# LiPo_Charger.net
KiCad netlist of a schematic drawn in Altium Designer
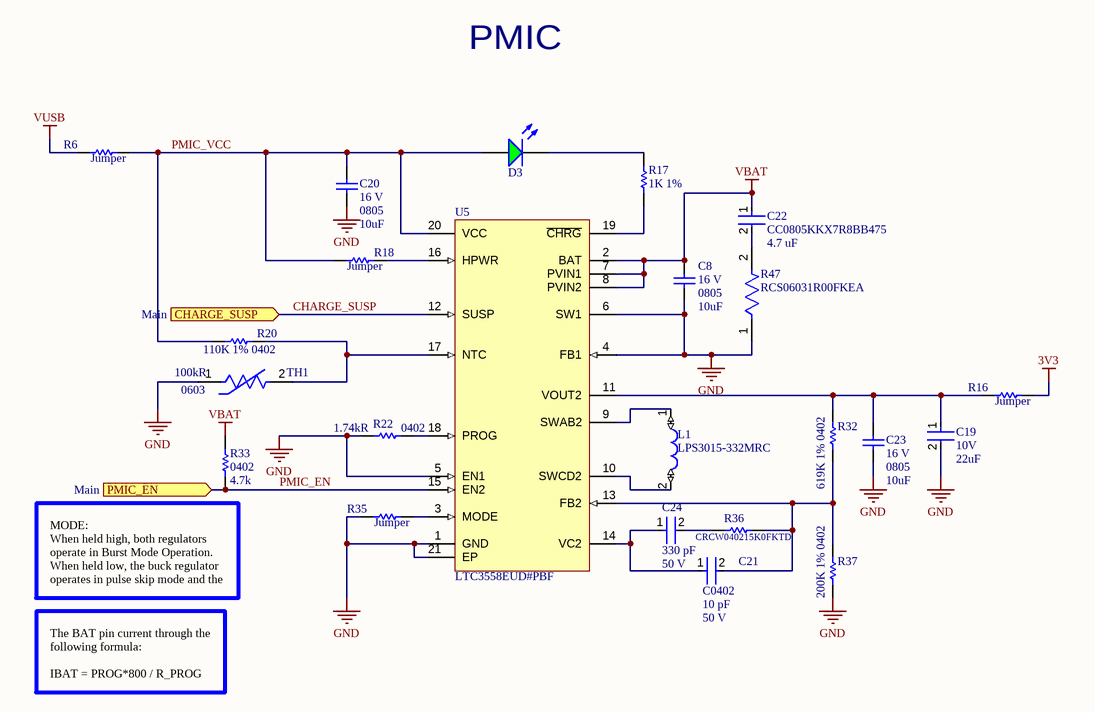
[diagram p0: LiPo_Charger.SchDoc]

(export (version "E")
  (design (tool "Eeschema 10.0.6"))
  (components
    (comp (ref "C8")
      (value "10uF")
      (footprint "CAPC0805(2012)145_N")
      (description "CAP 10uF 16V ±10% 0805 (2012 Metric) Thickness 1.45mm SMD")
      (fields
        (field (name "RATED VOLTAGE") "16 V")
        (field (name "CASE-EIA") "0805")
        (field (name "TOLERANCE") "Â±10%")
        (field (name "MANUFACTURER PART NUMBER") "CC0805KKX7R7BB106")
      )
      (libsource (lib "ProtoWatch_Compiled") (part "CMP-1036-04927-1"))
    )
    (comp (ref "C19")
      (value "LMK107BBJ226MA-T")
      (footprint "FP-LMK107B-A-MFG")
      (description "CAP CER 22UF 10V X5R 0603")
      (fields
        (field (name "TOLERANCE") "20%")
        (field (name "MANUFACTURER") "Taiyo Yuden")
        (field (name "VOLTAGE RATING") "10V")
        (field (name "CAPACITANCE") "22uF")
      )
      (libsource (lib "Altium Content Vault") (part "11868f565c42a9108669ba33697ecf6"))
    )
    (comp (ref "C20")
      (value "10uF")
      (footprint "CAPC0805(2012)145_N")
      (description "CAP 10uF 16V ±10% 0805 (2012 Metric) Thickness 1.45mm SMD")
      (fields
        (field (name "RATED VOLTAGE") "16 V")
        (field (name "CASE-EIA") "0805")
        (field (name "TOLERANCE") "Â±10%")
        (field (name "MANUFACTURER PART NUMBER") "CC0805KKX7R7BB106")
      )
      (libsource (lib "ProtoWatch_Compiled") (part "CMP-1036-04927-1"))
    )
    (comp (ref "C21")
      (value "10 pF")
      (footprint "FP-C0402-BB-MFG")
      (description "C0402 10 pF C0G 0.5 pF 50 V")
      (fields
        (field (name "MANUFACTURER") "Kemet")
        (field (name "PACKAGE") "C0402")
        (field (name "OCTOPART") "https://octopart.com/c0402c100d5gac-kemet-2680337")
        (field (name "VOLTAGE RATING") "50 V")
      )
      (libsource (lib "Altium Content Vault") (part "b4654b650e69147ec39a6b967a45e02"))
    )
    (comp (ref "C22")
      (value "CC0805KKX7R8BB475")
      (footprint "FP-CC0805-0_85-MFG")
      (description "CAP CER 4.7UF 25V X7R 0805")
      (fields
        (field (name "OCTOPART") "https://octopart.com/cc0805kkx7r8bb475-yageo-51849247")
        (field (name "CAPACITANCE") "4.7 uF")
        (field (name "MANUFACTURER") "Yageo")
      )
      (libsource (lib "Altium Content Vault") (part "11868f565c42a9108669ba33697ecf6"))
    )
    (comp (ref "C23")
      (value "10uF")
      (footprint "CAPC0805(2012)145_N")
      (description "CAP 10uF 16V ±10% 0805 (2012 Metric) Thickness 1.45mm SMD")
      (fields
        (field (name "RATED VOLTAGE") "16 V")
        (field (name "CASE-EIA") "0805")
        (field (name "TOLERANCE") "Â±10%")
        (field (name "MANUFACTURER PART NUMBER") "CC0805KKX7R7BB106")
      )
      (libsource (lib "ProtoWatch_Compiled") (part "CMP-1036-04927-1"))
    )
    (comp (ref "C24")
      (value "330 pF")
      (footprint "FP-CC0402-MFG")
      (description "CAP CER 330PF 50V X7R 0402")
      (fields
        (field (name "MANUFACTURER") "YAGEO")
        (field (name "MANUFACTURER PART NUMBER") "CC0402KRX7R9BB331")
        (field (name "VOLTAGE RATING") "50 V")
      )
      (libsource (lib "Altium Content Vault") (part "11868f565c42a9108669ba33697ecf6"))
    )
    (comp (ref "D3")
      (value "LTST-C170GKT")
      (footprint "LTST-C170GKT_V")
      (description "LED Uni-Color Green, 100 mW, 120 mA, -55 to 85 degC, 2-Pin SMD, RoHS, Tape and Reel")
      (fields (field (name "MANUFACTURER") "Lite-On"))
      (libsource (lib "Altium Content Vault") (part "LED-GREEN-AK-2"))
    )
    (comp (ref "L1")
      (value "LPS3015-332MRC")
      (footprint "ProtoWatch_PcbLib:LPS3015")
      (description "Power inductor, shielded, 20% tol, SMT, RoHS, lead-free, halogen-free")
      (fields (field (name "MF") "Coilcraft"))
      (libsource (lib "ProtoWatch_SchLib") (part "LPS3015-332MRC"))
    )
    (comp (ref "R6")
      (value "Jumper")
      (footprint "RESC0603(1608)_N")
      (description "Jumper 0603 (1608 Metric)")
      (fields (field (name "POWER") "None"))
      (libsource (lib "Altium Content Vault") (part "RES"))
    )
    (comp (ref "R16")
      (value "Jumper")
      (footprint "RESC0603(1608)_N")
      (description "Jumper 0603 (1608 Metric)")
      (fields (field (name "POWER") "None"))
      (libsource (lib "Altium Content Vault") (part "RES"))
    )
    (comp (ref "R17")
      (value "1K 1%")
      (footprint "RESC0603(1608)_N")
      (description "1K 0.1W 1% 0603 (1608 Metric)  SMD")
      (fields (field (name "TOLERANCE") "1 %") (field (name "POWER") "0.1 W"))
      (libsource (lib "Altium Content Vault") (part "RES"))
    )
    (comp (ref "R18")
      (value "Jumper")
      (footprint "RESC0603(1608)_N")
      (description "Jumper 0603 (1608 Metric)")
      (fields (field (name "POWER") "None"))
      (libsource (lib "Altium Content Vault") (part "RES"))
    )
    (comp (ref "R20")
      (value "110K 1% 0402")
      (footprint "RESC0402(1005)_M")
      (description "110K 0.063W 1% 0402 (1005 Metric)  SMD")
      (fields (field (name "TOLERANCE") "1 %") (field (name "POWER") "0.063 W"))
      (libsource (lib "Altium Content Vault") (part "RES"))
    )
    (comp (ref "R22")
      (value "CRCW04021K74FKED")
      (footprint "RESC1005X40X25LL05T05")
      (fields
        (field (name "MANUFACTURER") "Vishay Dale")
        (field (name "CASE/PACKAGE") "0402")
        (field (name "TOLERANCE") "1%")
        (field (name "RESISTANCE") "1.74kR")
      )
      (libsource (lib "Altium Content Vault") (part "RES"))
    )
    (comp (ref "R32")
      (value "619K 1% 0402")
      (footprint "RESC0402(1005)_L")
      (description "619K 0.063W 1% 0402 (1005 Metric)  SMD")
      (fields (field (name "POWER") "0.063 W") (field (name "TOLERANCE") "1 %"))
      (libsource (lib "Altium Content Vault") (part "RES"))
    )
    (comp (ref "R33")
      (value "RMCF0402JT4K70")
      (footprint "RESC1005X40X25LL10T15")
      (description "Chip Resistor, 4.7 KOhm, +/- 5%, 0.063 W, -55 to 155 degC, 0402 (1005 Metric), RoHS, Tape and Reel")
      (fields
        (field (name "MANUFACTURER") "Stackpole-Electronics-Inc.")
        (field (name "TOLERANCE") "±5%")
        (field (name "PACKAGE REFERENCE") "0402")
        (field (name "RESISTANCE (OHMS)") "4.7k")
      )
      (libsource (lib "Altium Content Vault") (part "RES-2"))
    )
    (comp (ref "R35")
      (value "Jumper")
      (footprint "RESC0603(1608)_N")
      (description "Jumper 0603 (1608 Metric)")
      (fields (field (name "POWER") "None"))
      (libsource (lib "Altium Content Vault") (part "RES"))
    )
    (comp (ref "R36")
      (value "CRCW040215K0FKTD")
      (footprint "RESC1005X40X25NL05T05")
      (fields (field (name "MANUFACTURER") "Vishay Dale"))
      (libsource (lib "Altium Content Vault") (part "RES"))
    )
    (comp (ref "R37")
      (value "200K 1% 0402")
      (footprint "RESC0402(1005)_L")
      (description "200K 0.063W 1% 0402 (1005 Metric)  SMD")
      (fields (field (name "TOLERANCE") "1 %") (field (name "POWER") "0.063 W"))
      (libsource (lib "Altium Content Vault") (part "RES"))
    )
    (comp (ref "R47")
      (value "RCS06031R00FKEA")
      (footprint "FP-RCS0603-e3-MFG")
      (description "RES SMD 1 OHM 1% 1/4W 0603")
      (fields (field (name "TOLERANCE") "1%"))
      (libsource (lib "Altium Content Vault") (part "1029c3af85768c4190bb7ad29bc67b5"))
    )
    (comp (ref "TH1")
      (value "NCP18WF104D03RB")
      (footprint "FP-NCP18-0_15-MFG")
      (description "NTC Thermistor for Temperature Sensor, 0603, 100kΩ, 0.5%, 0.032mA, 5V")
      (fields
        (field (name "TOLERANCE") "0.5%")
        (field (name "CASE CODE (IMPERIAL)") "0603")
        (field (name "RESISTANCE") "100kR")
      )
      (libsource (lib "Altium Content Vault") (part "3b148a6ebabc5fb4d708a66c052d352"))
    )
    (comp (ref "U5")
      (value "LTC3558EUD#PBF")
      (footprint "LT-UD-20_N")
      (fields (field (name "MANUFACTURER") "Linear Technology"))
      (libsource (lib "ProtoWatch_SchLib") (part "LTC3558EUD#PBF"))
    )
  )
  (nets
    (net (code "1") (name "/CHARGE_SUSP") (class "Default")
      (node (ref "U5") (pin "12") (pinfunction "SUSP_12") (pintype "input"))
    )
    (net (code "2") (name "/PMIC_EN") (class "Default")
      (node (ref "R33") (pin "1") (pinfunction "1_1") (pintype "passive"))
      (node (ref "U5") (pin "15") (pinfunction "EN2_15") (pintype "input"))
    )
    (net (code "3") (name "/PMIC_VCC") (class "Default")
      (node (ref "C20") (pin "2") (pinfunction "2_2") (pintype "passive"))
      (node (ref "D3") (pin "1") (pinfunction "A_1") (pintype "passive"))
      (node (ref "R18") (pin "1") (pinfunction "1_1") (pintype "passive"))
      (node (ref "R20") (pin "1") (pinfunction "1_1") (pintype "passive"))
      (node (ref "R6") (pin "2") (pinfunction "2_2") (pintype "passive"))
      (node (ref "U5") (pin "20") (pinfunction "VCC_20") (pintype "passive"))
    )
    (net (code "4") (name "3V3") (class "Default")
      (node (ref "R16") (pin "2") (pinfunction "2_2") (pintype "passive"))
    )
    (net (code "5") (name "GND") (class "Default")
      (node (ref "C19") (pin "2") (pinfunction "2_2") (pintype "passive"))
      (node (ref "C20") (pin "1") (pinfunction "1_1") (pintype "passive"))
      (node (ref "C23") (pin "1") (pinfunction "1_1") (pintype "passive"))
      (node (ref "C8") (pin "1") (pinfunction "1_1") (pintype "passive"))
      (node (ref "R22") (pin "1") (pinfunction "1_1") (pintype "passive"))
      (node (ref "R35") (pin "1") (pinfunction "1_1") (pintype "passive"))
      (node (ref "R37") (pin "2") (pinfunction "2_2") (pintype "passive"))
      (node (ref "R47") (pin "1") (pinfunction "1_1") (pintype "passive"))
      (node (ref "TH1") (pin "1") (pinfunction "1_1") (pintype "passive"))
      (node (ref "U5") (pin "1") (pinfunction "GND_1") (pintype "power_in"))
      (node (ref "U5") (pin "21") (pinfunction "EP_21") (pintype "power_in"))
      (node (ref "U5") (pin "4") (pinfunction "FB1_4") (pintype "input"))
      (node (ref "U5") (pin "5") (pinfunction "EN1_5") (pintype "input"))
      (node (ref "U5") (pin "6") (pinfunction "SW1_6") (pintype "power_in"))
    )
    (net (code "6") (name "Net-(C22-Pad2)") (class "Default")
      (node (ref "C22") (pin "2") (pinfunction "2_2") (pintype "passive"))
      (node (ref "R47") (pin "2") (pinfunction "2_2") (pintype "passive"))
    )
    (net (code "7") (name "Net-(C24-Pad2)") (class "Default")
      (node (ref "C24") (pin "2") (pinfunction "2_2") (pintype "passive"))
      (node (ref "R36") (pin "1") (pinfunction "1_1") (pintype "passive"))
    )
    (net (code "8") (name "Net-(D3-K)") (class "Default")
      (node (ref "D3") (pin "2") (pinfunction "K_2") (pintype "passive"))
      (node (ref "R17") (pin "1") (pinfunction "1_1") (pintype "passive"))
    )
    (net (code "9") (name "Net-(U5-FB2)") (class "Default")
      (node (ref "C21") (pin "2") (pinfunction "2_2") (pintype "passive"))
      (node (ref "R32") (pin "1") (pinfunction "1_1") (pintype "passive"))
      (node (ref "R36") (pin "2") (pinfunction "2_2") (pintype "passive"))
      (node (ref "R37") (pin "1") (pinfunction "1_1") (pintype "passive"))
      (node (ref "U5") (pin "13") (pinfunction "FB2_13") (pintype "input"))
    )
    (net (code "10") (name "Net-(U5-HPWR)") (class "Default")
      (node (ref "R18") (pin "2") (pinfunction "2_2") (pintype "passive"))
      (node (ref "U5") (pin "16") (pinfunction "HPWR_16") (pintype "input"))
    )
    (net (code "11") (name "Net-(U5-MODE)") (class "Default")
      (node (ref "R35") (pin "2") (pinfunction "2_2") (pintype "passive"))
      (node (ref "U5") (pin "3") (pinfunction "MODE_3") (pintype "input"))
    )
    (net (code "12") (name "Net-(U5-NTC)") (class "Default")
      (node (ref "R20") (pin "2") (pinfunction "2_2") (pintype "passive"))
      (node (ref "TH1") (pin "2") (pinfunction "2_2") (pintype "passive"))
      (node (ref "U5") (pin "17") (pinfunction "NTC_17") (pintype "input"))
    )
    (net (code "13") (name "Net-(U5-PROG)") (class "Default")
      (node (ref "R22") (pin "2") (pinfunction "2_2") (pintype "passive"))
      (node (ref "U5") (pin "18") (pinfunction "PROG_18") (pintype "input"))
    )
    (net (code "14") (name "Net-(U5-SWAB2)") (class "Default")
      (node (ref "L1") (pin "1") (pinfunction "1_1") (pintype "bidirectional"))
      (node (ref "U5") (pin "9") (pinfunction "SWAB2_9") (pintype "passive"))
    )
    (net (code "15") (name "Net-(U5-SWCD2)") (class "Default")
      (node (ref "L1") (pin "2") (pinfunction "2_2") (pintype "bidirectional"))
      (node (ref "U5") (pin "10") (pinfunction "SWCD2_10") (pintype "passive"))
    )
    (net (code "16") (name "Net-(U5-VC2)") (class "Default")
      (node (ref "C21") (pin "1") (pinfunction "1_1") (pintype "passive"))
      (node (ref "C24") (pin "1") (pinfunction "1_1") (pintype "passive"))
      (node (ref "U5") (pin "14") (pinfunction "VC2_14") (pintype "passive"))
    )
    (net (code "17") (name "Net-(U5-VOUT2)") (class "Default")
      (node (ref "C19") (pin "1") (pinfunction "1_1") (pintype "passive"))
      (node (ref "C23") (pin "2") (pinfunction "2_2") (pintype "passive"))
      (node (ref "R16") (pin "1") (pinfunction "1_1") (pintype "passive"))
      (node (ref "R32") (pin "2") (pinfunction "2_2") (pintype "passive"))
      (node (ref "U5") (pin "11") (pinfunction "VOUT2_11") (pintype "passive"))
    )
    (net (code "18") (name "Net-(U5-~{CHRG})") (class "Default")
      (node (ref "R17") (pin "2") (pinfunction "2_2") (pintype "passive"))
      (node (ref "U5") (pin "19") (pinfunction "~{CHRG}_19") (pintype "passive"))
    )
    (net (code "19") (name "VBAT") (class "Default")
      (node (ref "C22") (pin "1") (pinfunction "1_1") (pintype "passive"))
      (node (ref "C8") (pin "2") (pinfunction "2_2") (pintype "passive"))
      (node (ref "R33") (pin "2") (pinfunction "2_2") (pintype "passive"))
      (node (ref "U5") (pin "2") (pinfunction "BAT_2") (pintype "passive"))
      (node (ref "U5") (pin "7") (pinfunction "PVIN1_7") (pintype "passive"))
      (node (ref "U5") (pin "8") (pinfunction "PVIN2_8") (pintype "passive"))
    )
    (net (code "20") (name "VUSB") (class "Default")
      (node (ref "R6") (pin "1") (pinfunction "1_1") (pintype "passive"))
    )
  )
)
